# Top.net
KiCad netlist of a schematic drawn in Altium Designer
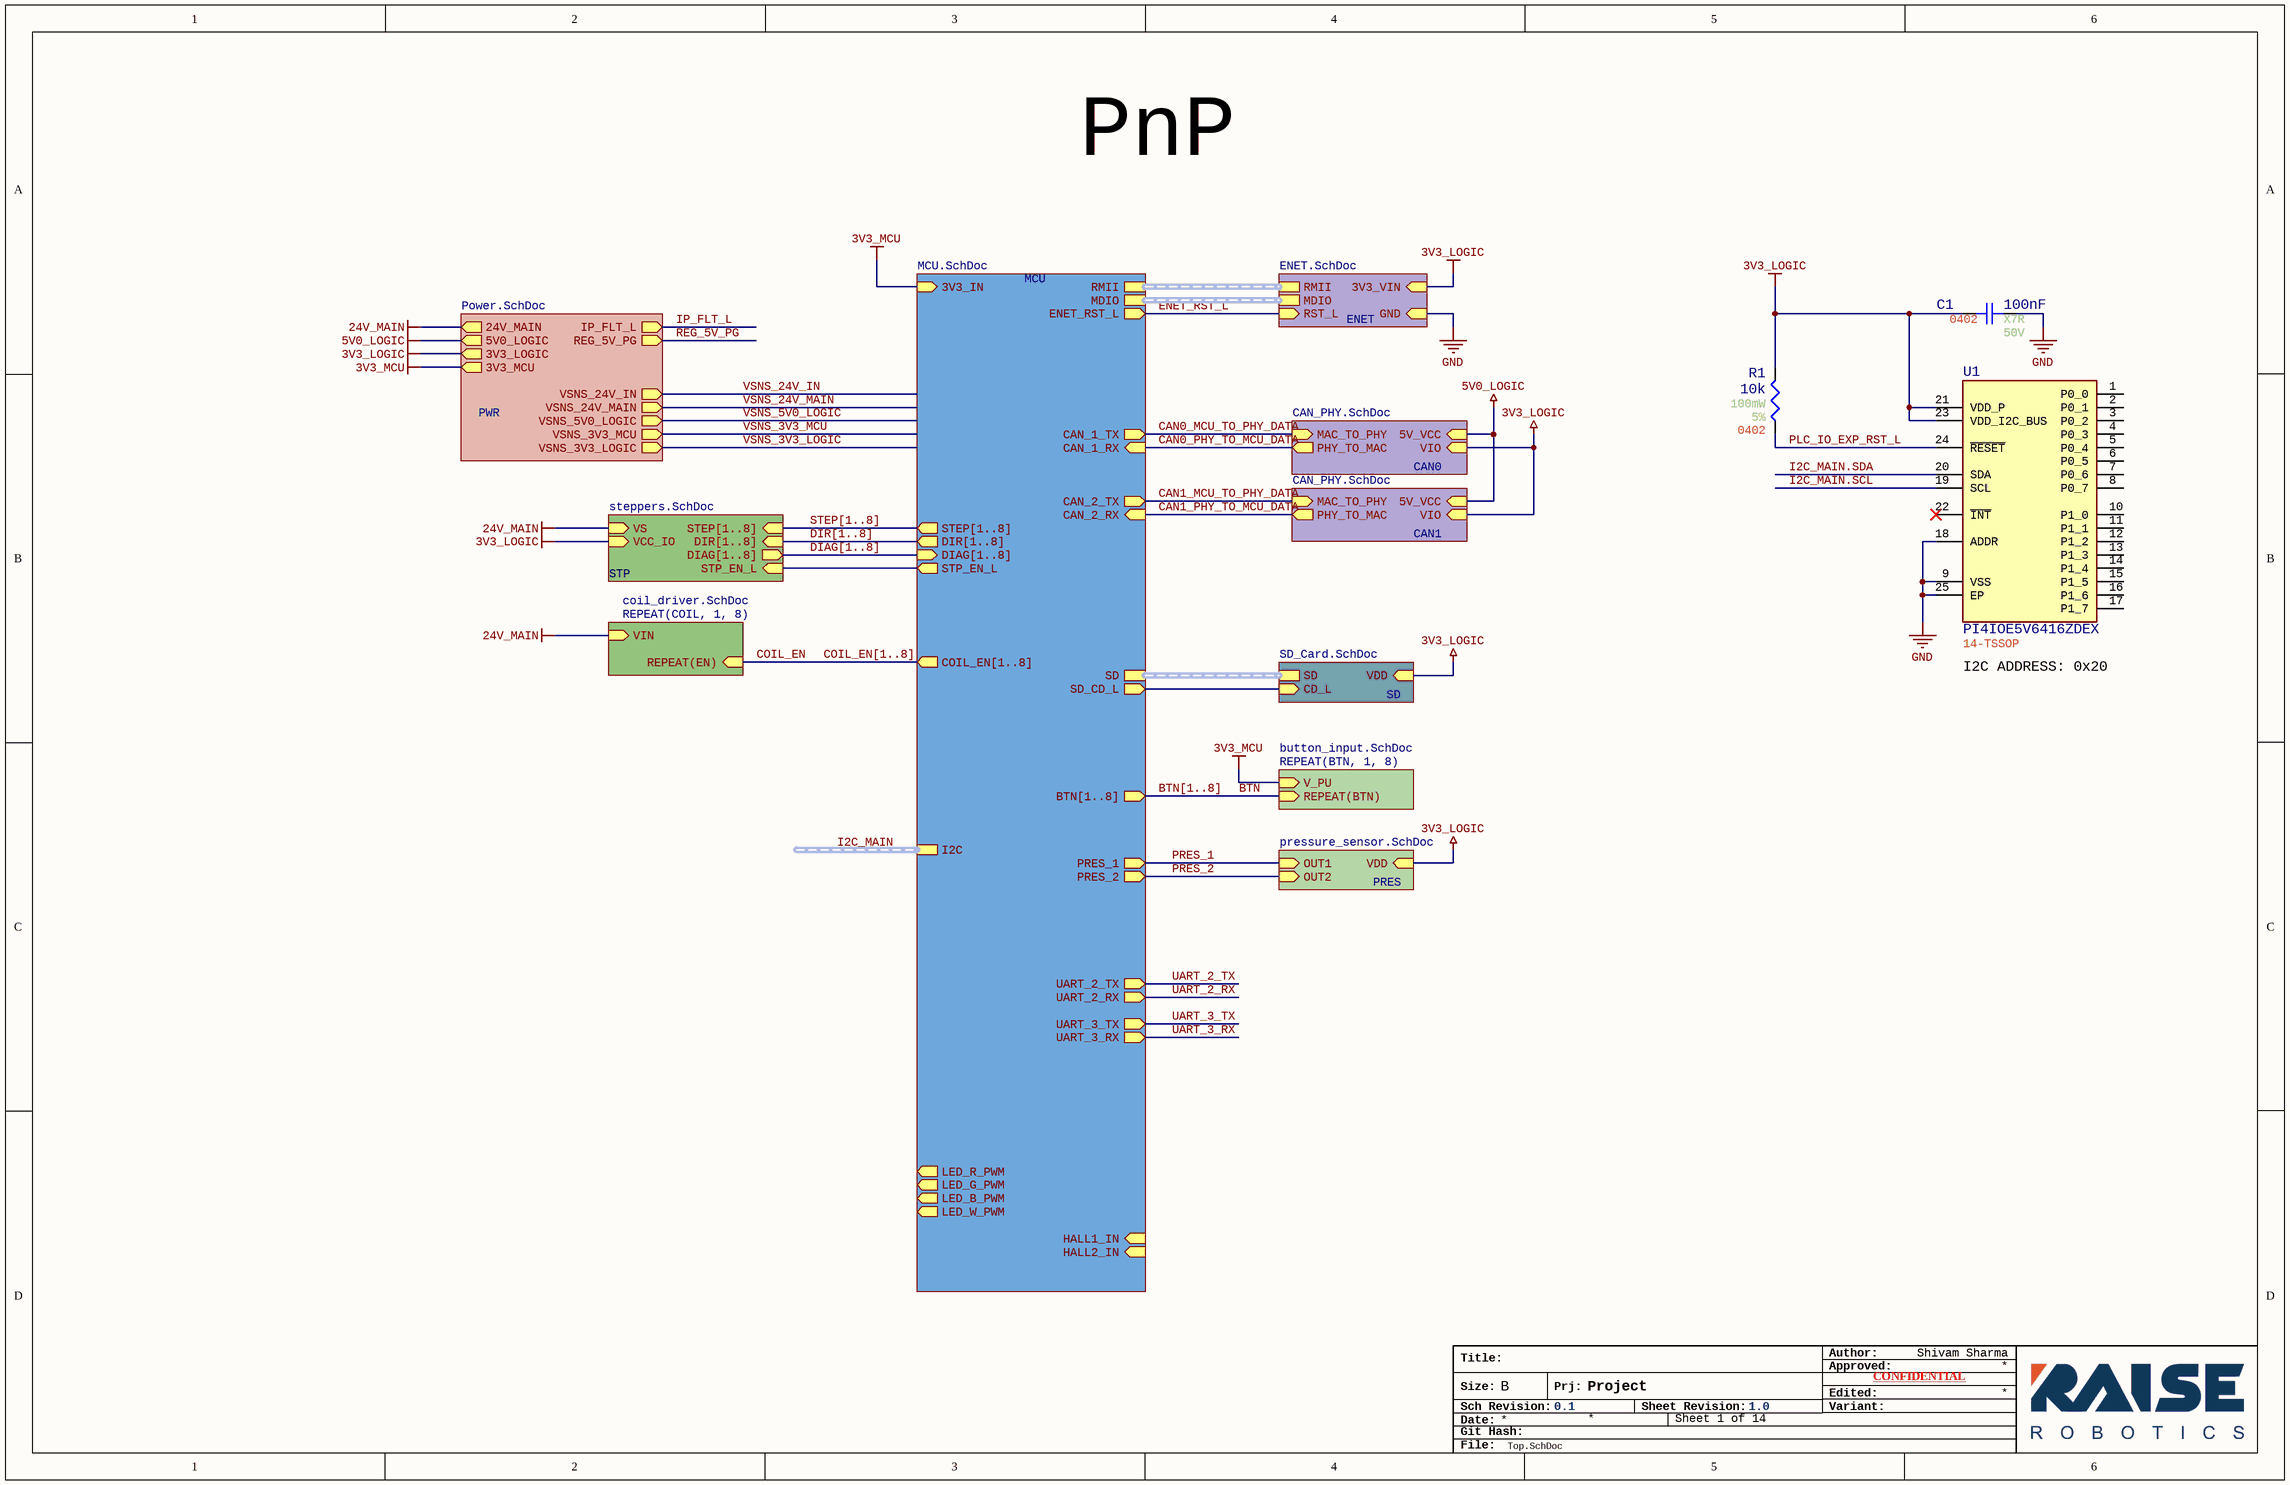
[diagram p0: Top.SchDoc]

(export (version "E")
  (design (tool "Eeschema 10.0.6"))
  (components
    (comp (ref "C1")
      (value "100nF")
      (footprint "Generic 0402 capacitor")
      (fields
        (field (name "TEMPERATURE COEFFICIENT") "X7R")
        (field (name "VOLTAGE RATING") "50V")
        (field (name "CASE/PACKAGE") "0402")
        (field (name "TOLERANCE") "10%")
        (field (name "Comment") "GRT155R71H104KE01D")
      )
      (libsource (lib "Raise Robotics") (part "Unpolarized Capacitor"))
    )
    (comp (ref "R1")
      (value "10k")
      (footprint "Generic 0402 Resistor")
      (description "Res Thick Film 0402 10K Ohm 5% 1/10W ±200ppm/°C Molded SMD Punched Carrier T/R")
      (fields
        (field (name "POWER") "100mW")
        (field (name "TOLERANCE") "5%")
        (field (name "CASE/PACKAGE") "0402")
        (field (name "Comment") "ERJ-2GEJ103X")
      )
      (libsource (lib "Raise Robotics") (part "Resistor"))
    )
    (comp (ref "U1")
      (value "PI4IOE5V6416ZDEX")
      (footprint "PI4IOE5V6416ZDEX")
      (description "16-bit I2C General Purpose IO Expander with Interrupt, Reset, -40 to 85 °C, RoHS")
      (fields (field (name "CASE/PACKAGE") "14-TSSOP"))
      (libsource (lib "Raise Robotics") (part "PI4IOE5V6416ZDEX"))
    )
  )
  (nets
    (net (code "55") (name "/I2C_MAIN.SCL") (class "Default")
      (node (ref "U1") (pin "19") (pinfunction "SCL_19") (pintype "passive"))
    )
    (net (code "56") (name "/I2C_MAIN.SDA") (class "Default")
      (node (ref "U1") (pin "20") (pinfunction "SDA_20") (pintype "passive"))
    )
    (net (code "63") (name "/PLC_IO_EXP_RST_L") (class "Default")
      (node (ref "R1") (pin "1") (pinfunction "1_1") (pintype "passive"))
      (node (ref "U1") (pin "24") (pinfunction "~{RESET}_24") (pintype "passive"))
    )
    (net (code "82") (name "3V3_LOGIC") (class "Default")
      (node (ref "C1") (pin "2") (pinfunction "2_2") (pintype "passive"))
      (node (ref "R1") (pin "2") (pinfunction "2_2") (pintype "passive"))
      (node (ref "U1") (pin "21") (pinfunction "VDD_P_21") (pintype "passive"))
      (node (ref "U1") (pin "23") (pinfunction "VDD_I2C_BUS_23") (pintype "passive"))
    )
    (net (code "86") (name "GND") (class "Default")
      (node (ref "C1") (pin "1") (pinfunction "1_1") (pintype "passive"))
      (node (ref "U1") (pin "18") (pinfunction "ADDR_18") (pintype "passive"))
      (node (ref "U1") (pin "25") (pinfunction "EP_25") (pintype "passive"))
      (node (ref "U1") (pin "9") (pinfunction "VSS_9") (pintype "passive"))
    )
    (net (code "87") (name "unconnected-(U1-P0_0-Pad1)") (class "Default")
      (node (ref "U1") (pin "1") (pinfunction "P0_0_1") (pintype "passive"))
    )
    (net (code "88") (name "unconnected-(U1-P0_1-Pad2)") (class "Default")
      (node (ref "U1") (pin "2") (pinfunction "P0_1_2") (pintype "passive"))
    )
    (net (code "89") (name "unconnected-(U1-P0_2-Pad3)") (class "Default")
      (node (ref "U1") (pin "3") (pinfunction "P0_2_3") (pintype "passive"))
    )
    (net (code "90") (name "unconnected-(U1-P0_3-Pad4)") (class "Default")
      (node (ref "U1") (pin "4") (pinfunction "P0_3_4") (pintype "passive"))
    )
    (net (code "91") (name "unconnected-(U1-P0_4-Pad5)") (class "Default")
      (node (ref "U1") (pin "5") (pinfunction "P0_4_5") (pintype "passive"))
    )
    (net (code "92") (name "unconnected-(U1-P0_5-Pad6)") (class "Default")
      (node (ref "U1") (pin "6") (pinfunction "P0_5_6") (pintype "passive"))
    )
    (net (code "93") (name "unconnected-(U1-P0_6-Pad7)") (class "Default")
      (node (ref "U1") (pin "7") (pinfunction "P0_6_7") (pintype "passive"))
    )
    (net (code "94") (name "unconnected-(U1-P0_7-Pad8)") (class "Default")
      (node (ref "U1") (pin "8") (pinfunction "P0_7_8") (pintype "passive"))
    )
    (net (code "95") (name "unconnected-(U1-P1_0-Pad10)") (class "Default")
      (node (ref "U1") (pin "10") (pinfunction "P1_0_10") (pintype "passive"))
    )
    (net (code "96") (name "unconnected-(U1-P1_1-Pad11)") (class "Default")
      (node (ref "U1") (pin "11") (pinfunction "P1_1_11") (pintype "passive"))
    )
    (net (code "97") (name "unconnected-(U1-P1_2-Pad12)") (class "Default")
      (node (ref "U1") (pin "12") (pinfunction "P1_2_12") (pintype "passive"))
    )
    (net (code "98") (name "unconnected-(U1-P1_3-Pad13)") (class "Default")
      (node (ref "U1") (pin "13") (pinfunction "P1_3_13") (pintype "passive"))
    )
    (net (code "99") (name "unconnected-(U1-P1_4-Pad14)") (class "Default")
      (node (ref "U1") (pin "14") (pinfunction "P1_4_14") (pintype "passive"))
    )
    (net (code "100") (name "unconnected-(U1-P1_5-Pad15)") (class "Default")
      (node (ref "U1") (pin "15") (pinfunction "P1_5_15") (pintype "passive"))
    )
    (net (code "101") (name "unconnected-(U1-P1_6-Pad16)") (class "Default")
      (node (ref "U1") (pin "16") (pinfunction "P1_6_16") (pintype "passive"))
    )
    (net (code "102") (name "unconnected-(U1-P1_7-Pad17)") (class "Default")
      (node (ref "U1") (pin "17") (pinfunction "P1_7_17") (pintype "passive"))
    )
    (net (code "103") (name "unconnected-(U1-~{INT}-Pad22)") (class "Default")
      (node (ref "U1") (pin "22") (pinfunction "~{INT}_22") (pintype "passive+no_connect"))
    )
  )
)
